# Fei-Fei.net
KiCad netlist of a schematic drawn in Altium Designer
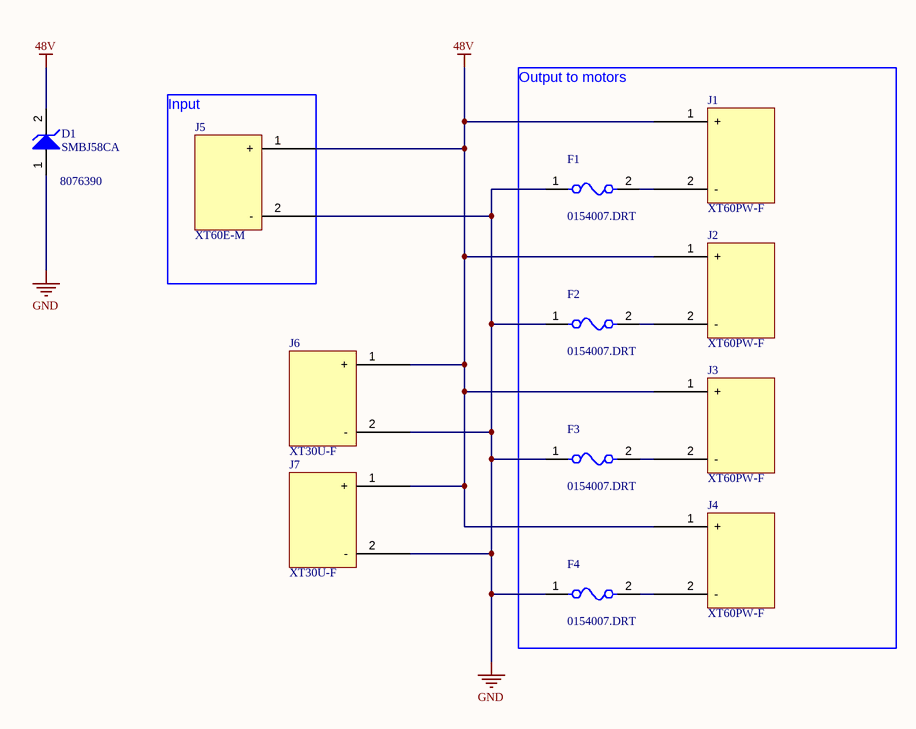
[diagram p0: Fei-Fei.SchDoc]

(export (version "E")
  (design (tool "Eeschema 10.0.6"))
  (components
    (comp (ref "D1")
      (value "SMBJ58CA")
      (footprint "DO-214AA")
      (description "Diode TVS Single Bi-Dir 58V 600W 2-Pin SMB")
      (fields
        (field (name "MANUFACTURER") "Diodes Incorporated")
        (field (name "MANUFACTURER PART NUMBER") "SMBJ54A-13-F")
        (field (name "SUPPLIER PART NUMBER 2") "8076390")
      )
      (libsource (lib "Schlib1") (part "SMBJ48A-13-F"))
    )
    (comp (ref "F1")
      (value "0154007.DRT")
      (footprint "FP-0154-MFG")
      (description "FUSE BRD MNT 7A 72VAC 60VDC 2SMD")
      (fields
        (field (name "OCTOPART") "https://octopart.com/0154007.drt-littelfuse-19644006")
        (field (name "MANUFACTURER") "Littelfuse Inc")
      )
      (libsource (lib "Altium Content Vault") (part "5bcf9b9f640e542cf0359d10258e979"))
    )
    (comp (ref "F2")
      (value "0154007.DRT")
      (footprint "FP-0154-MFG")
      (description "FUSE BRD MNT 7A 72VAC 60VDC 2SMD")
      (fields
        (field (name "OCTOPART") "https://octopart.com/0154007.drt-littelfuse-19644006")
        (field (name "MANUFACTURER") "Littelfuse Inc")
      )
      (libsource (lib "Altium Content Vault") (part "5bcf9b9f640e542cf0359d10258e979"))
    )
    (comp (ref "F3")
      (value "0154007.DRT")
      (footprint "FP-0154-MFG")
      (description "FUSE BRD MNT 7A 72VAC 60VDC 2SMD")
      (fields
        (field (name "OCTOPART") "https://octopart.com/0154007.drt-littelfuse-19644006")
        (field (name "MANUFACTURER") "Littelfuse Inc")
      )
      (libsource (lib "Altium Content Vault") (part "5bcf9b9f640e542cf0359d10258e979"))
    )
    (comp (ref "F4")
      (value "0154007.DRT")
      (footprint "FP-0154-MFG")
      (description "FUSE BRD MNT 7A 72VAC 60VDC 2SMD")
      (fields
        (field (name "OCTOPART") "https://octopart.com/0154007.drt-littelfuse-19644006")
        (field (name "MANUFACTURER") "Littelfuse Inc")
      )
      (libsource (lib "Altium Content Vault") (part "5bcf9b9f640e542cf0359d10258e979"))
    )
    (comp (ref "J1")
      (value "XT60PW-F")
      (footprint "XT60PW_F")
      (libsource (lib "Fei-Fei_Power_Distro_V0.3") (part "XT60PW-F"))
    )
    (comp (ref "J2")
      (value "XT60PW-F")
      (footprint "XT60PW_F")
      (libsource (lib "Fei-Fei_Power_Distro_V0.3") (part "XT60PW-F"))
    )
    (comp (ref "J3")
      (value "XT60PW-F")
      (footprint "XT60PW_F")
      (libsource (lib "Fei-Fei_Power_Distro_V0.3") (part "XT60PW-F"))
    )
    (comp (ref "J4")
      (value "XT60PW-F")
      (footprint "XT60PW_F")
      (libsource (lib "Fei-Fei_Power_Distro_V0.3") (part "XT60PW-F"))
    )
    (comp (ref "J5")
      (value "XT60E-M")
      (footprint "XT60E-M")
      (libsource (lib "Fei-Fei_Power_Distro_V0.3") (part "XT60E-M"))
    )
    (comp (ref "J6")
      (value "XT30U-F")
      (footprint "XT30U-F")
      (libsource (lib "Fei-Fei_Power_Distro_V0.3") (part "XT30U-F"))
    )
    (comp (ref "J7")
      (value "XT30U-F")
      (footprint "XT30U-F")
      (libsource (lib "Fei-Fei_Power_Distro_V0.3") (part "XT30U-F"))
    )
  )
  (nets
    (net (code "1") (name "48V") (class "Default")
      (node (ref "D1") (pin "2") (pinfunction "K_2") (pintype "passive"))
      (node (ref "J1") (pin "1") (pinfunction "+_1") (pintype "passive"))
      (node (ref "J2") (pin "1") (pinfunction "+_1") (pintype "passive"))
      (node (ref "J3") (pin "1") (pinfunction "+_1") (pintype "passive"))
      (node (ref "J4") (pin "1") (pinfunction "+_1") (pintype "passive"))
      (node (ref "J5") (pin "1") (pinfunction "+_1") (pintype "passive"))
      (node (ref "J6") (pin "1") (pinfunction "+_1") (pintype "passive"))
      (node (ref "J7") (pin "1") (pinfunction "+_1") (pintype "passive"))
    )
    (net (code "2") (name "GND") (class "Default")
      (node (ref "D1") (pin "1") (pinfunction "A_1") (pintype "passive"))
      (node (ref "F1") (pin "1") (pinfunction "1_1") (pintype "passive"))
      (node (ref "F2") (pin "1") (pinfunction "1_1") (pintype "passive"))
      (node (ref "F3") (pin "1") (pinfunction "1_1") (pintype "passive"))
      (node (ref "F4") (pin "1") (pinfunction "1_1") (pintype "passive"))
      (node (ref "J5") (pin "2") (pinfunction "-_2") (pintype "passive"))
      (node (ref "J6") (pin "2") (pinfunction "-_2") (pintype "passive"))
      (node (ref "J7") (pin "2") (pinfunction "-_2") (pintype "passive"))
    )
    (net (code "3") (name "Net-(J1--)") (class "Default")
      (node (ref "F1") (pin "2") (pinfunction "2_2") (pintype "passive"))
      (node (ref "J1") (pin "2") (pinfunction "-_2") (pintype "passive"))
    )
    (net (code "4") (name "Net-(J2--)") (class "Default")
      (node (ref "F2") (pin "2") (pinfunction "2_2") (pintype "passive"))
      (node (ref "J2") (pin "2") (pinfunction "-_2") (pintype "passive"))
    )
    (net (code "5") (name "Net-(J3--)") (class "Default")
      (node (ref "F3") (pin "2") (pinfunction "2_2") (pintype "passive"))
      (node (ref "J3") (pin "2") (pinfunction "-_2") (pintype "passive"))
    )
    (net (code "6") (name "Net-(J4--)") (class "Default")
      (node (ref "F4") (pin "2") (pinfunction "2_2") (pintype "passive"))
      (node (ref "J4") (pin "2") (pinfunction "-_2") (pintype "passive"))
    )
  )
)
